# fuenteSimetrica.net
KiCad netlist of a schematic drawn in EAGLE
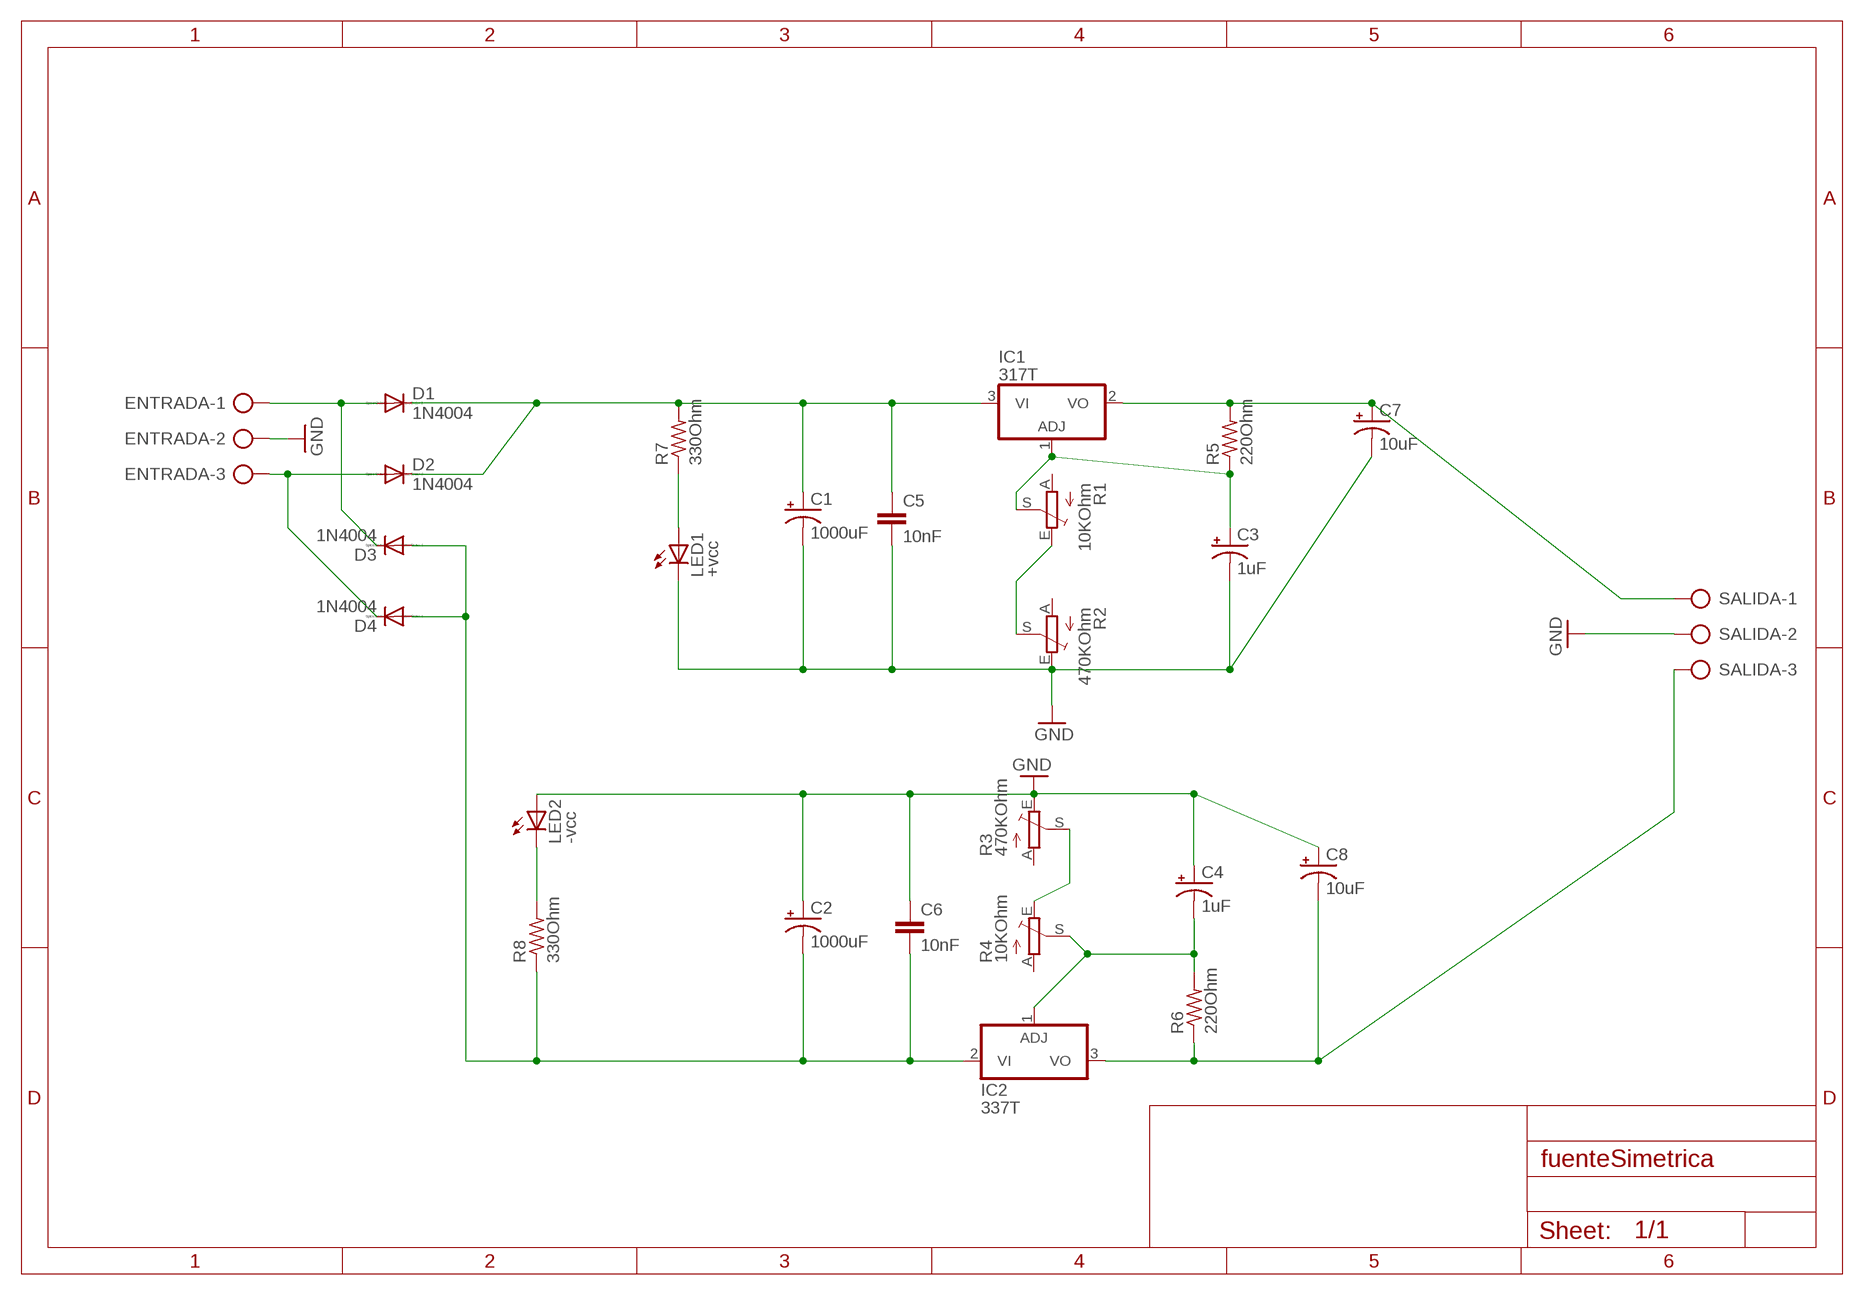
[diagram p0: schematic, sheet 1]

(export (version "E")
  (design (tool "Eeschema 10.0.6"))
  (components
    (comp (ref "C1")
      (value "1000uF")
      (footprint "eagle-import:E3,5-8")
      (libsource (lib "eagle-import") (part "CPOL-USE3.5-8"))
    )
    (comp (ref "C2")
      (value "1000uF")
      (footprint "eagle-import:E3,5-8")
      (libsource (lib "eagle-import") (part "CPOL-USE3.5-8"))
    )
    (comp (ref "C3")
      (value "1uF")
      (footprint "eagle-import:E2,5-6")
      (libsource (lib "eagle-import") (part "CPOL-USE2.5-6"))
    )
    (comp (ref "C4")
      (value "1uF")
      (footprint "eagle-import:E2,5-6")
      (libsource (lib "eagle-import") (part "CPOL-USE2.5-6"))
    )
    (comp (ref "C5")
      (value "10nF")
      (footprint "eagle-import:C050-030X075")
      (libsource (lib "eagle-import") (part "C-EU050-030X075"))
    )
    (comp (ref "C6")
      (value "10nF")
      (footprint "eagle-import:C050-030X075")
      (libsource (lib "eagle-import") (part "C-EU050-030X075"))
    )
    (comp (ref "C7")
      (value "10uF")
      (footprint "eagle-import:E2,5-6")
      (libsource (lib "eagle-import") (part "CPOL-USE2.5-6"))
    )
    (comp (ref "C8")
      (value "10uF")
      (footprint "eagle-import:E2,5-6")
      (libsource (lib "eagle-import") (part "CPOL-USE2.5-6"))
    )
    (comp (ref "D1")
      (value "1N4004")
      (footprint "eagle-import:DO41-10")
      (libsource (lib "eagle-import") (part "1N4004"))
    )
    (comp (ref "D2")
      (value "1N4004")
      (footprint "eagle-import:DO41-10")
      (libsource (lib "eagle-import") (part "1N4004"))
    )
    (comp (ref "D3")
      (value "1N4004")
      (footprint "eagle-import:DO41-10")
      (libsource (lib "eagle-import") (part "1N4004"))
    )
    (comp (ref "D4")
      (value "1N4004")
      (footprint "eagle-import:DO41-10")
      (libsource (lib "eagle-import") (part "1N4004"))
    )
    (comp (ref "ENTRADA")
      (value "AK500/3-H")
      (footprint "eagle-import:AK500_3-H")
      (libsource (lib "eagle-import") (part "AK500/3-H"))
    )
    (comp (ref "IC1")
      (value "317T")
      (footprint "eagle-import:TO220H")
      (libsource (lib "eagle-import") (part "317T"))
    )
    (comp (ref "IC2")
      (value "337T")
      (footprint "eagle-import:TO220H")
      (libsource (lib "eagle-import") (part "337T"))
    )
    (comp (ref "LED1")
      (value "+vcc")
      (footprint "eagle-import:LED5MM")
      (libsource (lib "eagle-import") (part "LED5MM"))
    )
    (comp (ref "LED2")
      (value "-vcc")
      (footprint "eagle-import:LED5MM")
      (libsource (lib "eagle-import") (part "LED5MM"))
    )
    (comp (ref "R1")
      (value "10KOhm")
      (footprint "eagle-import:RS3")
      (libsource (lib "eagle-import") (part "TRIM_EU-RS3"))
    )
    (comp (ref "R2")
      (value "470KOhm")
      (footprint "eagle-import:RS3")
      (libsource (lib "eagle-import") (part "TRIM_EU-RS3"))
    )
    (comp (ref "R3")
      (value "470KOhm")
      (footprint "eagle-import:RS3")
      (libsource (lib "eagle-import") (part "TRIM_EU-RS3"))
    )
    (comp (ref "R4")
      (value "10KOhm")
      (footprint "eagle-import:RS3")
      (libsource (lib "eagle-import") (part "TRIM_EU-RS3"))
    )
    (comp (ref "R5")
      (value "220Ohm")
      (footprint "eagle-import:0207_10")
      (libsource (lib "eagle-import") (part "R-US_0207/10"))
    )
    (comp (ref "R6")
      (value "220Ohm")
      (footprint "eagle-import:0207_10")
      (libsource (lib "eagle-import") (part "R-US_0207/10"))
    )
    (comp (ref "R7")
      (value "330Ohm")
      (footprint "eagle-import:0207_10")
      (libsource (lib "eagle-import") (part "R-US_0207/10"))
    )
    (comp (ref "R8")
      (value "330Ohm")
      (footprint "eagle-import:0207_10")
      (libsource (lib "eagle-import") (part "R-US_0207/10"))
    )
    (comp (ref "SALIDA")
      (value "AK500/3-H")
      (footprint "eagle-import:AK500_3-H")
      (libsource (lib "eagle-import") (part "AK500/3-H"))
    )
  )
  (nets
    (net (code "1") (name "GND") (class "Default")
      (node (ref "C1") (pin "-") (pinfunction "-_-") (pintype "passive"))
      (node (ref "C2") (pin "+") (pinfunction "+_+") (pintype "passive"))
      (node (ref "C3") (pin "-") (pinfunction "-_-") (pintype "passive"))
      (node (ref "C4") (pin "+") (pinfunction "+_+") (pintype "passive"))
      (node (ref "C5") (pin "2") (pinfunction "2_2") (pintype "passive"))
      (node (ref "C6") (pin "1") (pinfunction "1_1") (pintype "passive"))
      (node (ref "C7") (pin "-") (pinfunction "-_-") (pintype "passive"))
      (node (ref "C8") (pin "+") (pinfunction "+_+") (pintype "passive"))
      (node (ref "ENTRADA") (pin "2") (pinfunction "KL_2") (pintype "passive"))
      (node (ref "LED1") (pin "K") (pinfunction "C_K") (pintype "passive"))
      (node (ref "LED2") (pin "A") (pinfunction "A_A") (pintype "passive"))
      (node (ref "R2") (pin "E") (pinfunction "E_E") (pintype "passive"))
      (node (ref "R3") (pin "E") (pinfunction "E_E") (pintype "passive"))
      (node (ref "SALIDA") (pin "2") (pinfunction "KL_2") (pintype "passive"))
    )
    (net (code "2") (name "Net-(ENTRADAA-KL)") (class "Default")
      (node (ref "D1") (pin "A") (pinfunction "A_A") (pintype "passive"))
      (node (ref "D3") (pin "C") (pinfunction "C_C") (pintype "passive"))
      (node (ref "ENTRADA") (pin "1") (pinfunction "KL_1") (pintype "passive"))
    )
    (net (code "3") (name "Net-(ENTRADAC-KL)") (class "Default")
      (node (ref "D2") (pin "A") (pinfunction "A_A") (pintype "passive"))
      (node (ref "D4") (pin "C") (pinfunction "C_C") (pintype "passive"))
      (node (ref "ENTRADA") (pin "3") (pinfunction "KL_3") (pintype "passive"))
    )
    (net (code "4") (name "Net-(IC1-ADJ)") (class "Default")
      (node (ref "C3") (pin "+") (pinfunction "+_+") (pintype "passive"))
      (node (ref "IC1") (pin "1") (pinfunction "ADJ_1") (pintype "input"))
      (node (ref "R1") (pin "S") (pinfunction "S_S") (pintype "passive"))
      (node (ref "R5") (pin "1") (pinfunction "1_1") (pintype "passive"))
    )
    (net (code "5") (name "Net-(IC1-VI)") (class "Default")
      (node (ref "C1") (pin "+") (pinfunction "+_+") (pintype "passive"))
      (node (ref "C5") (pin "1") (pinfunction "1_1") (pintype "passive"))
      (node (ref "D1") (pin "C") (pinfunction "C_C") (pintype "passive"))
      (node (ref "D2") (pin "C") (pinfunction "C_C") (pintype "passive"))
      (node (ref "IC1") (pin "3") (pinfunction "VI_3") (pintype "input"))
      (node (ref "R7") (pin "2") (pinfunction "2_2") (pintype "passive"))
    )
    (net (code "6") (name "Net-(IC1-VO)") (class "Default")
      (node (ref "C7") (pin "+") (pinfunction "+_+") (pintype "passive"))
      (node (ref "IC1") (pin "2") (pinfunction "VO_2") (pintype "passive"))
      (node (ref "R5") (pin "2") (pinfunction "2_2") (pintype "passive"))
      (node (ref "SALIDA") (pin "1") (pinfunction "KL_1") (pintype "passive"))
    )
    (net (code "7") (name "Net-(IC2-ADJ)") (class "Default")
      (node (ref "C4") (pin "-") (pinfunction "-_-") (pintype "passive"))
      (node (ref "IC2") (pin "1") (pinfunction "ADJ_1") (pintype "input"))
      (node (ref "R4") (pin "S") (pinfunction "S_S") (pintype "passive"))
      (node (ref "R6") (pin "2") (pinfunction "2_2") (pintype "passive"))
    )
    (net (code "8") (name "Net-(IC2-VI)") (class "Default")
      (node (ref "C2") (pin "-") (pinfunction "-_-") (pintype "passive"))
      (node (ref "C6") (pin "2") (pinfunction "2_2") (pintype "passive"))
      (node (ref "D3") (pin "A") (pinfunction "A_A") (pintype "passive"))
      (node (ref "D4") (pin "A") (pinfunction "A_A") (pintype "passive"))
      (node (ref "IC2") (pin "2") (pinfunction "VI_2") (pintype "input"))
      (node (ref "R8") (pin "1") (pinfunction "1_1") (pintype "passive"))
    )
    (net (code "9") (name "Net-(IC2-VO)") (class "Default")
      (node (ref "C8") (pin "-") (pinfunction "-_-") (pintype "passive"))
      (node (ref "IC2") (pin "3") (pinfunction "VO_3") (pintype "passive"))
      (node (ref "R6") (pin "1") (pinfunction "1_1") (pintype "passive"))
      (node (ref "SALIDA") (pin "3") (pinfunction "KL_3") (pintype "passive"))
    )
    (net (code "10") (name "Net-(LED1-PadA)") (class "Default")
      (node (ref "LED1") (pin "A") (pinfunction "A_A") (pintype "passive"))
      (node (ref "R7") (pin "1") (pinfunction "1_1") (pintype "passive"))
    )
    (net (code "11") (name "Net-(LED2-C)") (class "Default")
      (node (ref "LED2") (pin "K") (pinfunction "C_K") (pintype "passive"))
      (node (ref "R8") (pin "2") (pinfunction "2_2") (pintype "passive"))
    )
    (net (code "12") (name "Net-(R1-PadE)") (class "Default")
      (node (ref "R1") (pin "E") (pinfunction "E_E") (pintype "passive"))
      (node (ref "R2") (pin "S") (pinfunction "S_S") (pintype "passive"))
    )
    (net (code "13") (name "Net-(R3-PadS)") (class "Default")
      (node (ref "R3") (pin "S") (pinfunction "S_S") (pintype "passive"))
      (node (ref "R4") (pin "E") (pinfunction "E_E") (pintype "passive"))
    )
    (net (code "14") (name "unconnected-(R1-PadA)") (class "Default")
      (node (ref "R1") (pin "A") (pinfunction "A_A") (pintype "passive"))
    )
    (net (code "15") (name "unconnected-(R2-PadA)") (class "Default")
      (node (ref "R2") (pin "A") (pinfunction "A_A") (pintype "passive"))
    )
    (net (code "16") (name "unconnected-(R3-PadA)") (class "Default")
      (node (ref "R3") (pin "A") (pinfunction "A_A") (pintype "passive"))
    )
    (net (code "17") (name "unconnected-(R4-PadA)") (class "Default")
      (node (ref "R4") (pin "A") (pinfunction "A_A") (pintype "passive"))
    )
  )
)
